# 8_Relay_Buzz_SCT013_75.net
KiCad netlist of a schematic drawn in EAGLE
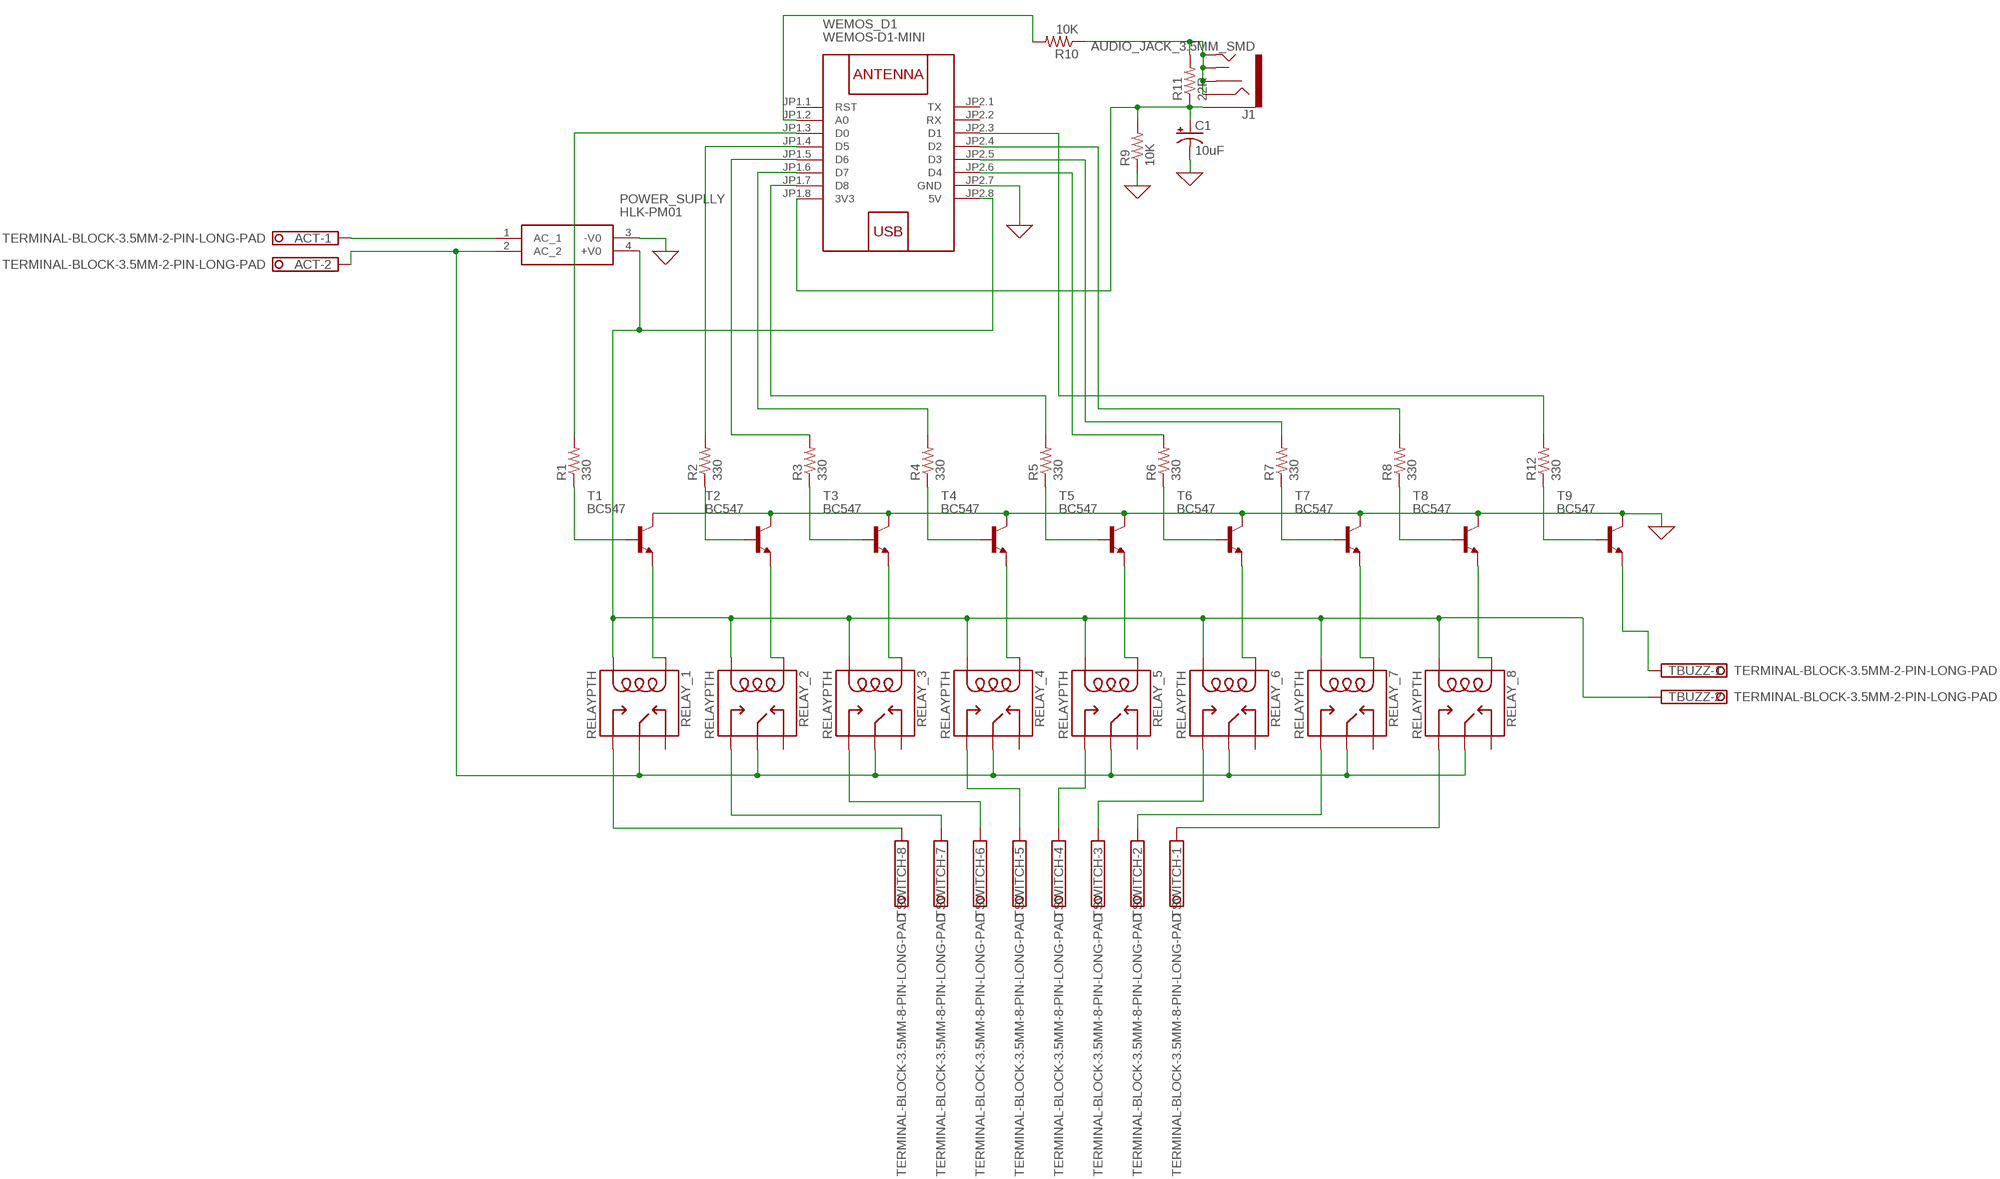
[diagram p0: schematic, sheet 1]

(export (version "E")
  (design (tool "Eeschema 10.0.6"))
  (components
    (comp (ref "ACT")
      (value "TERMINAL-BLOCK-3.5MM-2-PIN-LONG-PAD")
      (footprint "eagle-import:TERMINAL-BLOCK-2-PIN-3.5MM-LONG-PAD")
      (libsource (lib "eagle-import") (part "TERMINAL-BLOCK-3.5MM-2-PIN-LONG-PAD"))
    )
    (comp (ref "C1")
      (value "10uF")
      (footprint "eagle-import:E3,5-8")
      (libsource (lib "eagle-import") (part "CPOL-USE3.5-8"))
    )
    (comp (ref "J1")
      (value "AUDIO_JACK_3.5MM_SMD")
      (footprint "eagle-import:AUDIO-JACK-3.5MM-SMD")
      (libsource (lib "eagle-import") (part "AUDIO_JACK_3.5MM_SMD"))
    )
    (comp (ref "POWER_SUPLLY")
      (value "HLK-PM01")
      (footprint "eagle-import:HLKPM01")
      (fields (field (name "MF") "Hi-link") (field (name "MP") "hlk-pm01"))
      (libsource (lib "eagle-import") (part "HLK-PM01"))
    )
    (comp (ref "R1")
      (value "330")
      (footprint "eagle-import:0207_5V")
      (libsource (lib "eagle-import") (part "R-US_0207/5V"))
    )
    (comp (ref "R2")
      (value "330")
      (footprint "eagle-import:0207_5V")
      (libsource (lib "eagle-import") (part "R-US_0207/5V"))
    )
    (comp (ref "R3")
      (value "330")
      (footprint "eagle-import:0207_5V")
      (libsource (lib "eagle-import") (part "R-US_0207/5V"))
    )
    (comp (ref "R4")
      (value "330")
      (footprint "eagle-import:0207_5V")
      (libsource (lib "eagle-import") (part "R-US_0207/5V"))
    )
    (comp (ref "R5")
      (value "330")
      (footprint "eagle-import:0207_5V")
      (libsource (lib "eagle-import") (part "R-US_0207/5V"))
    )
    (comp (ref "R6")
      (value "330")
      (footprint "eagle-import:0207_5V")
      (libsource (lib "eagle-import") (part "R-US_0207/5V"))
    )
    (comp (ref "R7")
      (value "330")
      (footprint "eagle-import:0207_5V")
      (libsource (lib "eagle-import") (part "R-US_0207/5V"))
    )
    (comp (ref "R8")
      (value "330")
      (footprint "eagle-import:0207_5V")
      (libsource (lib "eagle-import") (part "R-US_0207/5V"))
    )
    (comp (ref "R9")
      (value "10K")
      (footprint "eagle-import:0207_5V")
      (libsource (lib "eagle-import") (part "R-US_0207/5V"))
    )
    (comp (ref "R10")
      (value "10K")
      (footprint "eagle-import:0207_5V")
      (libsource (lib "eagle-import") (part "R-US_0207/5V"))
    )
    (comp (ref "R11")
      (value "22R")
      (footprint "eagle-import:0207_5V")
      (libsource (lib "eagle-import") (part "R-US_0207/5V"))
    )
    (comp (ref "R12")
      (value "330")
      (footprint "eagle-import:0207_5V")
      (libsource (lib "eagle-import") (part "R-US_0207/5V"))
    )
    (comp (ref "RELAY_1")
      (value "RELAYPTH")
      (footprint "eagle-import:SRD-05VDC-SL-C")
      (libsource (lib "eagle-import") (part "RELAYPTH"))
    )
    (comp (ref "RELAY_2")
      (value "RELAYPTH")
      (footprint "eagle-import:SRD-05VDC-SL-C")
      (libsource (lib "eagle-import") (part "RELAYPTH"))
    )
    (comp (ref "RELAY_3")
      (value "RELAYPTH")
      (footprint "eagle-import:SRD-05VDC-SL-C")
      (libsource (lib "eagle-import") (part "RELAYPTH"))
    )
    (comp (ref "RELAY_4")
      (value "RELAYPTH")
      (footprint "eagle-import:SRD-05VDC-SL-C")
      (libsource (lib "eagle-import") (part "RELAYPTH"))
    )
    (comp (ref "RELAY_5")
      (value "RELAYPTH")
      (footprint "eagle-import:SRD-05VDC-SL-C")
      (libsource (lib "eagle-import") (part "RELAYPTH"))
    )
    (comp (ref "RELAY_6")
      (value "RELAYPTH")
      (footprint "eagle-import:SRD-05VDC-SL-C")
      (libsource (lib "eagle-import") (part "RELAYPTH"))
    )
    (comp (ref "RELAY_7")
      (value "RELAYPTH")
      (footprint "eagle-import:SRD-05VDC-SL-C")
      (libsource (lib "eagle-import") (part "RELAYPTH"))
    )
    (comp (ref "RELAY_8")
      (value "RELAYPTH")
      (footprint "eagle-import:SRD-05VDC-SL-C")
      (libsource (lib "eagle-import") (part "RELAYPTH"))
    )
    (comp (ref "T1")
      (value "BC547")
      (footprint "eagle-import:TO92")
      (libsource (lib "eagle-import") (part "BC547"))
    )
    (comp (ref "T2")
      (value "BC547")
      (footprint "eagle-import:TO92")
      (libsource (lib "eagle-import") (part "BC547"))
    )
    (comp (ref "T3")
      (value "BC547")
      (footprint "eagle-import:TO92")
      (libsource (lib "eagle-import") (part "BC547"))
    )
    (comp (ref "T4")
      (value "BC547")
      (footprint "eagle-import:TO92")
      (libsource (lib "eagle-import") (part "BC547"))
    )
    (comp (ref "T5")
      (value "BC547")
      (footprint "eagle-import:TO92")
      (libsource (lib "eagle-import") (part "BC547"))
    )
    (comp (ref "T6")
      (value "BC547")
      (footprint "eagle-import:TO92")
      (libsource (lib "eagle-import") (part "BC547"))
    )
    (comp (ref "T7")
      (value "BC547")
      (footprint "eagle-import:TO92")
      (libsource (lib "eagle-import") (part "BC547"))
    )
    (comp (ref "T8")
      (value "BC547")
      (footprint "eagle-import:TO92")
      (libsource (lib "eagle-import") (part "BC547"))
    )
    (comp (ref "T9")
      (value "BC547")
      (footprint "eagle-import:TO92")
      (libsource (lib "eagle-import") (part "BC547"))
    )
    (comp (ref "TBUZZ")
      (value "TERMINAL-BLOCK-3.5MM-2-PIN-LONG-PAD")
      (footprint "eagle-import:TERMINAL-BLOCK-2-PIN-3.5MM-LONG-PAD")
      (libsource (lib "eagle-import") (part "TERMINAL-BLOCK-3.5MM-2-PIN-LONG-PAD"))
    )
    (comp (ref "TSWITCH")
      (value "TERMINAL-BLOCK-3.5MM-8-PIN-LONG-PAD")
      (footprint "eagle-import:TERMINAL-BLOCK-8-PIN-3.5MM-LONG-PAD")
      (libsource (lib "eagle-import") (part "TERMINAL-BLOCK-3.5MM-8-PIN-LONG-PAD"))
    )
    (comp (ref "WEMOS_D1")
      (value "WEMOS-D1-MINI")
      (footprint "eagle-import:WEMOS-D1-MINI")
      (libsource (lib "eagle-import") (part "WEMOS-D1-MINI"))
    )
  )
  (nets
    (net (code "1") (name "GND") (class "Default")
      (node (ref "C1") (pin "-") (pinfunction "-_-") (pintype "passive"))
      (node (ref "POWER_SUPLLY") (pin "3") (pinfunction "-V0_3") (pintype "bidirectional"))
      (node (ref "R9") (pin "1") (pinfunction "1_1") (pintype "passive"))
      (node (ref "T1") (pin "3") (pinfunction "C_3") (pintype "passive"))
      (node (ref "T2") (pin "3") (pinfunction "C_3") (pintype "passive"))
      (node (ref "T3") (pin "3") (pinfunction "C_3") (pintype "passive"))
      (node (ref "T4") (pin "3") (pinfunction "C_3") (pintype "passive"))
      (node (ref "T5") (pin "3") (pinfunction "C_3") (pintype "passive"))
      (node (ref "T6") (pin "3") (pinfunction "C_3") (pintype "passive"))
      (node (ref "T7") (pin "3") (pinfunction "C_3") (pintype "passive"))
      (node (ref "T8") (pin "3") (pinfunction "C_3") (pintype "passive"))
      (node (ref "T9") (pin "3") (pinfunction "C_3") (pintype "passive"))
      (node (ref "WEMOS_D1") (pin "JP2.7") (pinfunction "GND_JP2.7") (pintype "power_in"))
    )
    (net (code "2") (name "Net-(ACTA-K)") (class "Default")
      (node (ref "ACT") (pin "1") (pinfunction "K_1") (pintype "passive"))
      (node (ref "POWER_SUPLLY") (pin "1") (pinfunction "AC_1_1") (pintype "bidirectional"))
    )
    (net (code "3") (name "Net-(ACTB-K)") (class "Default")
      (node (ref "ACT") (pin "2") (pinfunction "K_2") (pintype "passive"))
      (node (ref "POWER_SUPLLY") (pin "2") (pinfunction "AC_2_2") (pintype "bidirectional"))
      (node (ref "RELAY_1") (pin "SWCOMMON") (pinfunction "SWCOMMON_SWCOMMON") (pintype "bidirectional"))
      (node (ref "RELAY_2") (pin "SWCOMMON") (pinfunction "SWCOMMON_SWCOMMON") (pintype "bidirectional"))
      (node (ref "RELAY_3") (pin "SWCOMMON") (pinfunction "SWCOMMON_SWCOMMON") (pintype "bidirectional"))
      (node (ref "RELAY_4") (pin "SWCOMMON") (pinfunction "SWCOMMON_SWCOMMON") (pintype "bidirectional"))
      (node (ref "RELAY_5") (pin "SWCOMMON") (pinfunction "SWCOMMON_SWCOMMON") (pintype "bidirectional"))
      (node (ref "RELAY_6") (pin "SWCOMMON") (pinfunction "SWCOMMON_SWCOMMON") (pintype "bidirectional"))
      (node (ref "RELAY_7") (pin "SWCOMMON") (pinfunction "SWCOMMON_SWCOMMON") (pintype "bidirectional"))
      (node (ref "RELAY_8") (pin "SWCOMMON") (pinfunction "SWCOMMON_SWCOMMON") (pintype "bidirectional"))
    )
    (net (code "4") (name "Net-(J1-PadRING)") (class "Default")
      (node (ref "J1") (pin "RING") (pinfunction "RING_RING") (pintype "bidirectional"))
      (node (ref "J1") (pin "RSH") (pinfunction "RSH_RSH") (pintype "bidirectional"))
      (node (ref "J1") (pin "TIP") (pinfunction "TIP_TIP") (pintype "bidirectional"))
      (node (ref "J1") (pin "TSH") (pinfunction "TSH_TSH") (pintype "bidirectional"))
      (node (ref "R10") (pin "1") (pinfunction "1_1") (pintype "passive"))
      (node (ref "R11") (pin "2") (pinfunction "2_2") (pintype "passive"))
    )
    (net (code "5") (name "Net-(POWER_SUPLLY-+V0)") (class "Default")
      (node (ref "POWER_SUPLLY") (pin "4") (pinfunction "+V0_4") (pintype "bidirectional"))
      (node (ref "RELAY_1") (pin "COIL0") (pinfunction "COIL0_COIL0") (pintype "bidirectional"))
      (node (ref "RELAY_2") (pin "COIL0") (pinfunction "COIL0_COIL0") (pintype "bidirectional"))
      (node (ref "RELAY_3") (pin "COIL0") (pinfunction "COIL0_COIL0") (pintype "bidirectional"))
      (node (ref "RELAY_4") (pin "COIL0") (pinfunction "COIL0_COIL0") (pintype "bidirectional"))
      (node (ref "RELAY_5") (pin "COIL0") (pinfunction "COIL0_COIL0") (pintype "bidirectional"))
      (node (ref "RELAY_6") (pin "COIL0") (pinfunction "COIL0_COIL0") (pintype "bidirectional"))
      (node (ref "RELAY_7") (pin "COIL0") (pinfunction "COIL0_COIL0") (pintype "bidirectional"))
      (node (ref "RELAY_8") (pin "COIL0") (pinfunction "COIL0_COIL0") (pintype "bidirectional"))
      (node (ref "TBUZZ") (pin "2") (pinfunction "K_2") (pintype "passive"))
      (node (ref "WEMOS_D1") (pin "JP2.8") (pinfunction "5V_JP2.8") (pintype "power_in"))
    )
    (net (code "6") (name "Net-(T1-B)") (class "Default")
      (node (ref "R1") (pin "1") (pinfunction "1_1") (pintype "passive"))
      (node (ref "T1") (pin "2") (pinfunction "B_2") (pintype "passive"))
    )
    (net (code "7") (name "Net-(T1-E)") (class "Default")
      (node (ref "RELAY_1") (pin "COIL1") (pinfunction "COIL1_COIL1") (pintype "bidirectional"))
      (node (ref "T1") (pin "1") (pinfunction "E_1") (pintype "passive"))
    )
    (net (code "8") (name "Net-(T2-B)") (class "Default")
      (node (ref "R2") (pin "1") (pinfunction "1_1") (pintype "passive"))
      (node (ref "T2") (pin "2") (pinfunction "B_2") (pintype "passive"))
    )
    (net (code "9") (name "Net-(T2-E)") (class "Default")
      (node (ref "RELAY_2") (pin "COIL1") (pinfunction "COIL1_COIL1") (pintype "bidirectional"))
      (node (ref "T2") (pin "1") (pinfunction "E_1") (pintype "passive"))
    )
    (net (code "10") (name "Net-(T3-B)") (class "Default")
      (node (ref "R3") (pin "1") (pinfunction "1_1") (pintype "passive"))
      (node (ref "T3") (pin "2") (pinfunction "B_2") (pintype "passive"))
    )
    (net (code "11") (name "Net-(T3-E)") (class "Default")
      (node (ref "RELAY_3") (pin "COIL1") (pinfunction "COIL1_COIL1") (pintype "bidirectional"))
      (node (ref "T3") (pin "1") (pinfunction "E_1") (pintype "passive"))
    )
    (net (code "12") (name "Net-(T4-B)") (class "Default")
      (node (ref "R4") (pin "1") (pinfunction "1_1") (pintype "passive"))
      (node (ref "T4") (pin "2") (pinfunction "B_2") (pintype "passive"))
    )
    (net (code "13") (name "Net-(T4-E)") (class "Default")
      (node (ref "RELAY_4") (pin "COIL1") (pinfunction "COIL1_COIL1") (pintype "bidirectional"))
      (node (ref "T4") (pin "1") (pinfunction "E_1") (pintype "passive"))
    )
    (net (code "14") (name "Net-(T5-B)") (class "Default")
      (node (ref "R5") (pin "1") (pinfunction "1_1") (pintype "passive"))
      (node (ref "T5") (pin "2") (pinfunction "B_2") (pintype "passive"))
    )
    (net (code "15") (name "Net-(T5-E)") (class "Default")
      (node (ref "RELAY_5") (pin "COIL1") (pinfunction "COIL1_COIL1") (pintype "bidirectional"))
      (node (ref "T5") (pin "1") (pinfunction "E_1") (pintype "passive"))
    )
    (net (code "16") (name "Net-(T6-B)") (class "Default")
      (node (ref "R6") (pin "1") (pinfunction "1_1") (pintype "passive"))
      (node (ref "T6") (pin "2") (pinfunction "B_2") (pintype "passive"))
    )
    (net (code "17") (name "Net-(T6-E)") (class "Default")
      (node (ref "RELAY_6") (pin "COIL1") (pinfunction "COIL1_COIL1") (pintype "bidirectional"))
      (node (ref "T6") (pin "1") (pinfunction "E_1") (pintype "passive"))
    )
    (net (code "18") (name "Net-(T7-B)") (class "Default")
      (node (ref "R7") (pin "1") (pinfunction "1_1") (pintype "passive"))
      (node (ref "T7") (pin "2") (pinfunction "B_2") (pintype "passive"))
    )
    (net (code "19") (name "Net-(T7-E)") (class "Default")
      (node (ref "RELAY_7") (pin "COIL1") (pinfunction "COIL1_COIL1") (pintype "bidirectional"))
      (node (ref "T7") (pin "1") (pinfunction "E_1") (pintype "passive"))
    )
    (net (code "20") (name "Net-(T8-B)") (class "Default")
      (node (ref "R8") (pin "1") (pinfunction "1_1") (pintype "passive"))
      (node (ref "T8") (pin "2") (pinfunction "B_2") (pintype "passive"))
    )
    (net (code "21") (name "Net-(T8-E)") (class "Default")
      (node (ref "RELAY_8") (pin "COIL1") (pinfunction "COIL1_COIL1") (pintype "bidirectional"))
      (node (ref "T8") (pin "1") (pinfunction "E_1") (pintype "passive"))
    )
    (net (code "22") (name "Net-(T9-B)") (class "Default")
      (node (ref "R12") (pin "1") (pinfunction "1_1") (pintype "passive"))
      (node (ref "T9") (pin "2") (pinfunction "B_2") (pintype "passive"))
    )
    (net (code "23") (name "Net-(T9-E)") (class "Default")
      (node (ref "T9") (pin "1") (pinfunction "E_1") (pintype "passive"))
      (node (ref "TBUZZ") (pin "1") (pinfunction "K_1") (pintype "passive"))
    )
    (net (code "24") (name "Net-(TSWITCHA-K)") (class "Default")
      (node (ref "RELAY_8") (pin "SWOPEN") (pinfunction "SWOPEN_SWOPEN") (pintype "bidirectional"))
      (node (ref "TSWITCH") (pin "1") (pinfunction "K_1") (pintype "passive"))
    )
    (net (code "25") (name "Net-(TSWITCHB-K)") (class "Default")
      (node (ref "RELAY_7") (pin "SWOPEN") (pinfunction "SWOPEN_SWOPEN") (pintype "bidirectional"))
      (node (ref "TSWITCH") (pin "2") (pinfunction "K_2") (pintype "passive"))
    )
    (net (code "26") (name "Net-(TSWITCHC-K)") (class "Default")
      (node (ref "RELAY_6") (pin "SWOPEN") (pinfunction "SWOPEN_SWOPEN") (pintype "bidirectional"))
      (node (ref "TSWITCH") (pin "3") (pinfunction "K_3") (pintype "passive"))
    )
    (net (code "27") (name "Net-(TSWITCHD-K)") (class "Default")
      (node (ref "RELAY_5") (pin "SWOPEN") (pinfunction "SWOPEN_SWOPEN") (pintype "bidirectional"))
      (node (ref "TSWITCH") (pin "4") (pinfunction "K_4") (pintype "passive"))
    )
    (net (code "28") (name "Net-(TSWITCHE-K)") (class "Default")
      (node (ref "RELAY_4") (pin "SWOPEN") (pinfunction "SWOPEN_SWOPEN") (pintype "bidirectional"))
      (node (ref "TSWITCH") (pin "5") (pinfunction "K_5") (pintype "passive"))
    )
    (net (code "29") (name "Net-(TSWITCHF-K)") (class "Default")
      (node (ref "RELAY_3") (pin "SWOPEN") (pinfunction "SWOPEN_SWOPEN") (pintype "bidirectional"))
      (node (ref "TSWITCH") (pin "6") (pinfunction "K_6") (pintype "passive"))
    )
    (net (code "30") (name "Net-(TSWITCHG-K)") (class "Default")
      (node (ref "RELAY_2") (pin "SWOPEN") (pinfunction "SWOPEN_SWOPEN") (pintype "bidirectional"))
      (node (ref "TSWITCH") (pin "7") (pinfunction "K_7") (pintype "passive"))
    )
    (net (code "31") (name "Net-(TSWITCHH-K)") (class "Default")
      (node (ref "RELAY_1") (pin "SWOPEN") (pinfunction "SWOPEN_SWOPEN") (pintype "bidirectional"))
      (node (ref "TSWITCH") (pin "8") (pinfunction "K_8") (pintype "passive"))
    )
    (net (code "32") (name "Net-(WEMOS_D1-3V3)") (class "Default")
      (node (ref "C1") (pin "+") (pinfunction "+_+") (pintype "passive"))
      (node (ref "J1") (pin "SLEEVE") (pinfunction "SLEEVE_SLEEVE") (pintype "bidirectional"))
      (node (ref "R11") (pin "1") (pinfunction "1_1") (pintype "passive"))
      (node (ref "R9") (pin "2") (pinfunction "2_2") (pintype "passive"))
      (node (ref "WEMOS_D1") (pin "JP1.8") (pinfunction "3V3_JP1.8") (pintype "power_in"))
    )
    (net (code "33") (name "Net-(WEMOS_D1-A0)") (class "Default")
      (node (ref "R10") (pin "2") (pinfunction "2_2") (pintype "passive"))
      (node (ref "WEMOS_D1") (pin "JP1.2") (pinfunction "A0_JP1.2") (pintype "bidirectional"))
    )
    (net (code "34") (name "Net-(WEMOS_D1-D0)") (class "Default")
      (node (ref "R1") (pin "2") (pinfunction "2_2") (pintype "passive"))
      (node (ref "WEMOS_D1") (pin "JP1.3") (pinfunction "D0_JP1.3") (pintype "bidirectional"))
    )
    (net (code "35") (name "Net-(WEMOS_D1-D1)") (class "Default")
      (node (ref "R12") (pin "2") (pinfunction "2_2") (pintype "passive"))
      (node (ref "WEMOS_D1") (pin "JP2.3") (pinfunction "D1_JP2.3") (pintype "bidirectional"))
    )
    (net (code "36") (name "Net-(WEMOS_D1-D2)") (class "Default")
      (node (ref "R8") (pin "2") (pinfunction "2_2") (pintype "passive"))
      (node (ref "WEMOS_D1") (pin "JP2.4") (pinfunction "D2_JP2.4") (pintype "bidirectional"))
    )
    (net (code "37") (name "Net-(WEMOS_D1-D3)") (class "Default")
      (node (ref "R7") (pin "2") (pinfunction "2_2") (pintype "passive"))
      (node (ref "WEMOS_D1") (pin "JP2.5") (pinfunction "D3_JP2.5") (pintype "bidirectional"))
    )
    (net (code "38") (name "Net-(WEMOS_D1-D4)") (class "Default")
      (node (ref "R6") (pin "2") (pinfunction "2_2") (pintype "passive"))
      (node (ref "WEMOS_D1") (pin "JP2.6") (pinfunction "D4_JP2.6") (pintype "bidirectional"))
    )
    (net (code "39") (name "Net-(WEMOS_D1-D5)") (class "Default")
      (node (ref "R2") (pin "2") (pinfunction "2_2") (pintype "passive"))
      (node (ref "WEMOS_D1") (pin "JP1.4") (pinfunction "D5_JP1.4") (pintype "bidirectional"))
    )
    (net (code "40") (name "Net-(WEMOS_D1-D6)") (class "Default")
      (node (ref "R3") (pin "2") (pinfunction "2_2") (pintype "passive"))
      (node (ref "WEMOS_D1") (pin "JP1.5") (pinfunction "D6_JP1.5") (pintype "bidirectional"))
    )
    (net (code "41") (name "Net-(WEMOS_D1-D7)") (class "Default")
      (node (ref "R4") (pin "2") (pinfunction "2_2") (pintype "passive"))
      (node (ref "WEMOS_D1") (pin "JP1.6") (pinfunction "D7_JP1.6") (pintype "bidirectional"))
    )
    (net (code "42") (name "Net-(WEMOS_D1-D8)") (class "Default")
      (node (ref "R5") (pin "2") (pinfunction "2_2") (pintype "passive"))
      (node (ref "WEMOS_D1") (pin "JP1.7") (pinfunction "D8_JP1.7") (pintype "bidirectional"))
    )
    (net (code "43") (name "unconnected-(RELAY_1-SWCLOSE-PadSWCLOSED)") (class "Default")
      (node (ref "RELAY_1") (pin "SWCLOSED") (pinfunction "SWCLOSE_SWCLOSED") (pintype "bidirectional"))
    )
    (net (code "44") (name "unconnected-(RELAY_2-SWCLOSE-PadSWCLOSED)") (class "Default")
      (node (ref "RELAY_2") (pin "SWCLOSED") (pinfunction "SWCLOSE_SWCLOSED") (pintype "bidirectional"))
    )
    (net (code "45") (name "unconnected-(RELAY_3-SWCLOSE-PadSWCLOSED)") (class "Default")
      (node (ref "RELAY_3") (pin "SWCLOSED") (pinfunction "SWCLOSE_SWCLOSED") (pintype "bidirectional"))
    )
    (net (code "46") (name "unconnected-(RELAY_4-SWCLOSE-PadSWCLOSED)") (class "Default")
      (node (ref "RELAY_4") (pin "SWCLOSED") (pinfunction "SWCLOSE_SWCLOSED") (pintype "bidirectional"))
    )
    (net (code "47") (name "unconnected-(RELAY_5-SWCLOSE-PadSWCLOSED)") (class "Default")
      (node (ref "RELAY_5") (pin "SWCLOSED") (pinfunction "SWCLOSE_SWCLOSED") (pintype "bidirectional"))
    )
    (net (code "48") (name "unconnected-(RELAY_6-SWCLOSE-PadSWCLOSED)") (class "Default")
      (node (ref "RELAY_6") (pin "SWCLOSED") (pinfunction "SWCLOSE_SWCLOSED") (pintype "bidirectional"))
    )
    (net (code "49") (name "unconnected-(RELAY_7-SWCLOSE-PadSWCLOSED)") (class "Default")
      (node (ref "RELAY_7") (pin "SWCLOSED") (pinfunction "SWCLOSE_SWCLOSED") (pintype "bidirectional"))
    )
    (net (code "50") (name "unconnected-(RELAY_8-SWCLOSE-PadSWCLOSED)") (class "Default")
      (node (ref "RELAY_8") (pin "SWCLOSED") (pinfunction "SWCLOSE_SWCLOSED") (pintype "bidirectional"))
    )
    (net (code "51") (name "unconnected-(WEMOS_D1-RST-PadJP1.1)") (class "Default")
      (node (ref "WEMOS_D1") (pin "JP1.1") (pinfunction "RST_JP1.1") (pintype "bidirectional"))
    )
    (net (code "52") (name "unconnected-(WEMOS_D1-RX-PadJP2.2)") (class "Default")
      (node (ref "WEMOS_D1") (pin "JP2.2") (pinfunction "RX_JP2.2") (pintype "bidirectional"))
    )
    (net (code "53") (name "unconnected-(WEMOS_D1-TX-PadJP2.1)") (class "Default")
      (node (ref "WEMOS_D1") (pin "JP2.1") (pinfunction "TX_JP2.1") (pintype "bidirectional"))
    )
  )
)
